# 4_periferals.net
KiCad netlist of a schematic drawn in Altium Designer
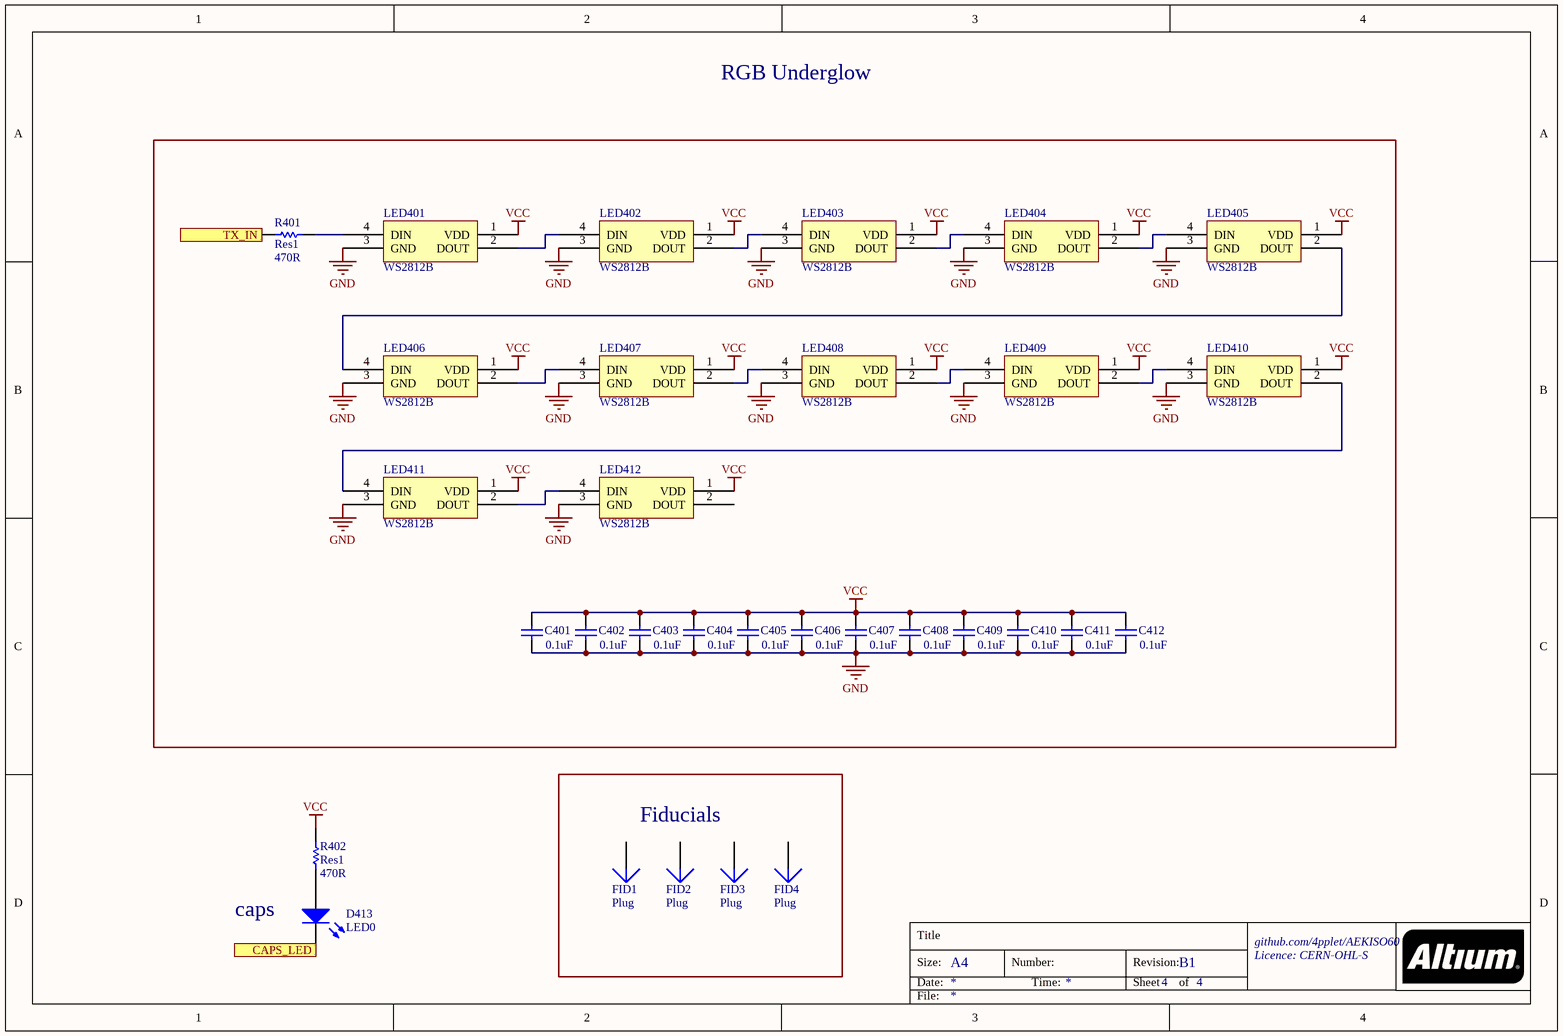
[diagram p0: 4_periferals.SchDoc]

(export (version "E")
  (design (tool "Eeschema 10.0.6"))
  (components
    (comp (ref "C401")
      (value "0.1uF")
      (footprint "C0603[1608]")
      (description "Capacitor")
      (fields (field (name "LCSC PART #") "C14663") (field (name "MRF.PART") "CC0603KRX7R9BB104"))
      (libsource (lib "Miscellaneous Devices") (part "Cap"))
    )
    (comp (ref "C402")
      (value "0.1uF")
      (footprint "C0603[1608]")
      (description "Capacitor")
      (fields (field (name "LCSC PART #") "C14663") (field (name "MRF.PART") "CC0603KRX7R9BB104"))
      (libsource (lib "Miscellaneous Devices") (part "Cap"))
    )
    (comp (ref "C403")
      (value "0.1uF")
      (footprint "C0603[1608]")
      (description "Capacitor")
      (fields (field (name "LCSC PART #") "C14663") (field (name "MRF.PART") "CC0603KRX7R9BB104"))
      (libsource (lib "Miscellaneous Devices") (part "Cap"))
    )
    (comp (ref "C404")
      (value "0.1uF")
      (footprint "C0603[1608]")
      (description "Capacitor")
      (fields (field (name "LCSC PART #") "C14663") (field (name "MRF.PART") "CC0603KRX7R9BB104"))
      (libsource (lib "Miscellaneous Devices") (part "Cap"))
    )
    (comp (ref "C405")
      (value "0.1uF")
      (footprint "C0603[1608]")
      (description "Capacitor")
      (fields (field (name "LCSC PART #") "C14663") (field (name "MRF.PART") "CC0603KRX7R9BB104"))
      (libsource (lib "Miscellaneous Devices") (part "Cap"))
    )
    (comp (ref "C406")
      (value "0.1uF")
      (footprint "C0603[1608]")
      (description "Capacitor")
      (fields (field (name "LCSC PART #") "C14663") (field (name "MRF.PART") "CC0603KRX7R9BB104"))
      (libsource (lib "Miscellaneous Devices") (part "Cap"))
    )
    (comp (ref "C407")
      (value "0.1uF")
      (footprint "C0603[1608]")
      (description "Capacitor")
      (fields (field (name "LCSC PART #") "C14663") (field (name "MRF.PART") "CC0603KRX7R9BB104"))
      (libsource (lib "Miscellaneous Devices") (part "Cap"))
    )
    (comp (ref "C408")
      (value "0.1uF")
      (footprint "C0603[1608]")
      (description "Capacitor")
      (fields (field (name "LCSC PART #") "C14663") (field (name "MRF.PART") "CC0603KRX7R9BB104"))
      (libsource (lib "Miscellaneous Devices") (part "Cap"))
    )
    (comp (ref "C409")
      (value "0.1uF")
      (footprint "C0603[1608]")
      (description "Capacitor")
      (fields (field (name "LCSC PART #") "C14663") (field (name "MRF.PART") "CC0603KRX7R9BB104"))
      (libsource (lib "Miscellaneous Devices") (part "Cap"))
    )
    (comp (ref "C410")
      (value "0.1uF")
      (footprint "C0603[1608]")
      (description "Capacitor")
      (fields (field (name "LCSC PART #") "C14663") (field (name "MRF.PART") "CC0603KRX7R9BB104"))
      (libsource (lib "Miscellaneous Devices") (part "Cap"))
    )
    (comp (ref "C411")
      (value "0.1uF")
      (footprint "C0603[1608]")
      (description "Capacitor")
      (fields (field (name "LCSC PART #") "C14663") (field (name "MRF.PART") "CC0603KRX7R9BB104"))
      (libsource (lib "Miscellaneous Devices") (part "Cap"))
    )
    (comp (ref "C412")
      (value "0.1uF")
      (footprint "C0603[1608]")
      (description "Capacitor")
      (fields (field (name "LCSC PART #") "C14663") (field (name "MRF.PART") "CC0603KRX7R9BB104"))
      (libsource (lib "Miscellaneous Devices") (part "Cap"))
    )
    (comp (ref "D413")
      (value "LED0")
      (footprint "SWITCH_LED - 1U")
      (description "Typical INFRARED GaAs LED")
      (libsource (lib "Miscellaneous Devices") (part "LED0"))
    )
    (comp (ref "FID1")
      (value "Plug")
      (footprint "Fiducial_Nordic")
      (libsource (lib "Miscellaneous Connectors") (part "Plug"))
    )
    (comp (ref "FID2")
      (value "Plug")
      (footprint "Fiducial_Nordic")
      (libsource (lib "Miscellaneous Connectors") (part "Plug"))
    )
    (comp (ref "FID3")
      (value "Plug")
      (footprint "Fiducial_Nordic")
      (libsource (lib "Miscellaneous Connectors") (part "Plug"))
    )
    (comp (ref "FID4")
      (value "Plug")
      (footprint "Fiducial_Nordic")
      (libsource (lib "Miscellaneous Connectors") (part "Plug"))
    )
    (comp (ref "LED401")
      (value "WS2812B")
      (footprint "WS2812B")
      (fields (field (name "LCSC PART #") "C2920042") (field (name "MRF.PART") "WS2812E-V5"))
      (libsource (lib "Keebs") (part "WS2812B"))
    )
    (comp (ref "LED402")
      (value "WS2812B")
      (footprint "WS2812B")
      (fields (field (name "LCSC PART #") "C2920042") (field (name "MRF.PART") "WS2812E-V5"))
      (libsource (lib "Keebs") (part "WS2812B"))
    )
    (comp (ref "LED403")
      (value "WS2812B")
      (footprint "WS2812B")
      (fields (field (name "LCSC PART #") "C2920042") (field (name "MRF.PART") "WS2812E-V5"))
      (libsource (lib "Keebs") (part "WS2812B"))
    )
    (comp (ref "LED404")
      (value "WS2812B")
      (footprint "WS2812B")
      (fields (field (name "LCSC PART #") "C2920042") (field (name "MRF.PART") "WS2812E-V5"))
      (libsource (lib "Keebs") (part "WS2812B"))
    )
    (comp (ref "LED405")
      (value "WS2812B")
      (footprint "WS2812B")
      (fields (field (name "LCSC PART #") "C2920042") (field (name "MRF.PART") "WS2812E-V5"))
      (libsource (lib "Keebs") (part "WS2812B"))
    )
    (comp (ref "LED406")
      (value "WS2812B")
      (footprint "WS2812B")
      (fields (field (name "LCSC PART #") "C2920042") (field (name "MRF.PART") "WS2812E-V5"))
      (libsource (lib "Keebs") (part "WS2812B"))
    )
    (comp (ref "LED407")
      (value "WS2812B")
      (footprint "WS2812B")
      (fields (field (name "LCSC PART #") "C2920042") (field (name "MRF.PART") "WS2812E-V5"))
      (libsource (lib "Keebs") (part "WS2812B"))
    )
    (comp (ref "LED408")
      (value "WS2812B")
      (footprint "WS2812B")
      (fields (field (name "LCSC PART #") "C2920042") (field (name "MRF.PART") "WS2812E-V5"))
      (libsource (lib "Keebs") (part "WS2812B"))
    )
    (comp (ref "LED409")
      (value "WS2812B")
      (footprint "WS2812B")
      (fields (field (name "LCSC PART #") "C2920042") (field (name "MRF.PART") "WS2812E-V5"))
      (libsource (lib "Keebs") (part "WS2812B"))
    )
    (comp (ref "LED410")
      (value "WS2812B")
      (footprint "WS2812B")
      (fields (field (name "LCSC PART #") "C2920042") (field (name "MRF.PART") "WS2812E-V5"))
      (libsource (lib "Keebs") (part "WS2812B"))
    )
    (comp (ref "LED411")
      (value "WS2812B")
      (footprint "WS2812B")
      (fields (field (name "LCSC PART #") "C2920042") (field (name "MRF.PART") "WS2812E-V5"))
      (libsource (lib "Keebs") (part "WS2812B"))
    )
    (comp (ref "LED412")
      (value "WS2812B")
      (footprint "WS2812B")
      (fields (field (name "LCSC PART #") "C2920042") (field (name "MRF.PART") "WS2812E-V5"))
      (libsource (lib "Keebs") (part "WS2812B"))
    )
    (comp (ref "R401")
      (value "Res1")
      (footprint "R0603[1608]")
      (description "Resistor")
      (fields
        (field (name "ALTIUM_VALUE") "470R")
        (field (name "LCSC PART #") "C23179")
        (field (name "MRF.PART") "0603WAF4700T5E")
      )
      (libsource (lib "Miscellaneous Devices") (part "Res1"))
    )
    (comp (ref "R402")
      (value "Res1")
      (footprint "R0603[1608] - THT")
      (description "Resistor")
      (fields
        (field (name "ALTIUM_VALUE") "470R")
        (field (name "LCSC PART #") "C23179")
        (field (name "MRF.PART") "0603WAF4700T5E")
      )
      (libsource (lib "Miscellaneous Devices") (part "Res1"))
    )
  )
  (nets
    (net (code "1") (name "/CAPS_LED") (class "Default")
      (node (ref "D413") (pin "2") (pinfunction "K_2") (pintype "passive"))
    )
    (net (code "2") (name "/TX_IN") (class "Default")
      (node (ref "R401") (pin "1") (pinfunction "1_1") (pintype "passive"))
    )
    (net (code "3") (name "GND") (class "Default")
      (node (ref "C401") (pin "1") (pinfunction "1_1") (pintype "passive"))
      (node (ref "C402") (pin "1") (pinfunction "1_1") (pintype "passive"))
      (node (ref "C403") (pin "1") (pinfunction "1_1") (pintype "passive"))
      (node (ref "C404") (pin "1") (pinfunction "1_1") (pintype "passive"))
      (node (ref "C405") (pin "1") (pinfunction "1_1") (pintype "passive"))
      (node (ref "C406") (pin "1") (pinfunction "1_1") (pintype "passive"))
      (node (ref "C407") (pin "1") (pinfunction "1_1") (pintype "passive"))
      (node (ref "C408") (pin "1") (pinfunction "1_1") (pintype "passive"))
      (node (ref "C409") (pin "1") (pinfunction "1_1") (pintype "passive"))
      (node (ref "C410") (pin "1") (pinfunction "1_1") (pintype "passive"))
      (node (ref "C411") (pin "1") (pinfunction "1_1") (pintype "passive"))
      (node (ref "C412") (pin "1") (pinfunction "1_1") (pintype "passive"))
      (node (ref "LED401") (pin "3") (pinfunction "GND_3") (pintype "passive"))
      (node (ref "LED402") (pin "3") (pinfunction "GND_3") (pintype "passive"))
      (node (ref "LED403") (pin "3") (pinfunction "GND_3") (pintype "passive"))
      (node (ref "LED404") (pin "3") (pinfunction "GND_3") (pintype "passive"))
      (node (ref "LED405") (pin "3") (pinfunction "GND_3") (pintype "passive"))
      (node (ref "LED406") (pin "3") (pinfunction "GND_3") (pintype "passive"))
      (node (ref "LED407") (pin "3") (pinfunction "GND_3") (pintype "passive"))
      (node (ref "LED408") (pin "3") (pinfunction "GND_3") (pintype "passive"))
      (node (ref "LED409") (pin "3") (pinfunction "GND_3") (pintype "passive"))
      (node (ref "LED410") (pin "3") (pinfunction "GND_3") (pintype "passive"))
      (node (ref "LED411") (pin "3") (pinfunction "GND_3") (pintype "passive"))
      (node (ref "LED412") (pin "3") (pinfunction "GND_3") (pintype "passive"))
    )
    (net (code "4") (name "Net-(D413-A)") (class "Default")
      (node (ref "D413") (pin "1") (pinfunction "A_1") (pintype "passive"))
      (node (ref "R402") (pin "1") (pinfunction "1_1") (pintype "passive"))
    )
    (net (code "5") (name "Net-(LED401-DIN)") (class "Default")
      (node (ref "LED401") (pin "4") (pinfunction "DIN_4") (pintype "passive"))
      (node (ref "R401") (pin "2") (pinfunction "2_2") (pintype "passive"))
    )
    (net (code "6") (name "Net-(LED401-DOUT)") (class "Default")
      (node (ref "LED401") (pin "2") (pinfunction "DOUT_2") (pintype "passive"))
      (node (ref "LED402") (pin "4") (pinfunction "DIN_4") (pintype "passive"))
    )
    (net (code "7") (name "Net-(LED402-DOUT)") (class "Default")
      (node (ref "LED402") (pin "2") (pinfunction "DOUT_2") (pintype "passive"))
      (node (ref "LED403") (pin "4") (pinfunction "DIN_4") (pintype "passive"))
    )
    (net (code "8") (name "Net-(LED403-DOUT)") (class "Default")
      (node (ref "LED403") (pin "2") (pinfunction "DOUT_2") (pintype "passive"))
      (node (ref "LED404") (pin "4") (pinfunction "DIN_4") (pintype "passive"))
    )
    (net (code "9") (name "Net-(LED404-DOUT)") (class "Default")
      (node (ref "LED404") (pin "2") (pinfunction "DOUT_2") (pintype "passive"))
      (node (ref "LED405") (pin "4") (pinfunction "DIN_4") (pintype "passive"))
    )
    (net (code "10") (name "Net-(LED405-DOUT)") (class "Default")
      (node (ref "LED405") (pin "2") (pinfunction "DOUT_2") (pintype "passive"))
      (node (ref "LED406") (pin "4") (pinfunction "DIN_4") (pintype "passive"))
    )
    (net (code "11") (name "Net-(LED406-DOUT)") (class "Default")
      (node (ref "LED406") (pin "2") (pinfunction "DOUT_2") (pintype "passive"))
      (node (ref "LED407") (pin "4") (pinfunction "DIN_4") (pintype "passive"))
    )
    (net (code "12") (name "Net-(LED407-DOUT)") (class "Default")
      (node (ref "LED407") (pin "2") (pinfunction "DOUT_2") (pintype "passive"))
      (node (ref "LED408") (pin "4") (pinfunction "DIN_4") (pintype "passive"))
    )
    (net (code "13") (name "Net-(LED408-DOUT)") (class "Default")
      (node (ref "LED408") (pin "2") (pinfunction "DOUT_2") (pintype "passive"))
      (node (ref "LED409") (pin "4") (pinfunction "DIN_4") (pintype "passive"))
    )
    (net (code "14") (name "Net-(LED409-DOUT)") (class "Default")
      (node (ref "LED409") (pin "2") (pinfunction "DOUT_2") (pintype "passive"))
      (node (ref "LED410") (pin "4") (pinfunction "DIN_4") (pintype "passive"))
    )
    (net (code "15") (name "Net-(LED410-DOUT)") (class "Default")
      (node (ref "LED410") (pin "2") (pinfunction "DOUT_2") (pintype "passive"))
      (node (ref "LED411") (pin "4") (pinfunction "DIN_4") (pintype "passive"))
    )
    (net (code "16") (name "Net-(LED411-DOUT)") (class "Default")
      (node (ref "LED411") (pin "2") (pinfunction "DOUT_2") (pintype "passive"))
      (node (ref "LED412") (pin "4") (pinfunction "DIN_4") (pintype "passive"))
    )
    (net (code "17") (name "VCC") (class "Default")
      (node (ref "C401") (pin "2") (pinfunction "2_2") (pintype "passive"))
      (node (ref "C402") (pin "2") (pinfunction "2_2") (pintype "passive"))
      (node (ref "C403") (pin "2") (pinfunction "2_2") (pintype "passive"))
      (node (ref "C404") (pin "2") (pinfunction "2_2") (pintype "passive"))
      (node (ref "C405") (pin "2") (pinfunction "2_2") (pintype "passive"))
      (node (ref "C406") (pin "2") (pinfunction "2_2") (pintype "passive"))
      (node (ref "C407") (pin "2") (pinfunction "2_2") (pintype "passive"))
      (node (ref "C408") (pin "2") (pinfunction "2_2") (pintype "passive"))
      (node (ref "C409") (pin "2") (pinfunction "2_2") (pintype "passive"))
      (node (ref "C410") (pin "2") (pinfunction "2_2") (pintype "passive"))
      (node (ref "C411") (pin "2") (pinfunction "2_2") (pintype "passive"))
      (node (ref "C412") (pin "2") (pinfunction "2_2") (pintype "passive"))
      (node (ref "LED401") (pin "1") (pinfunction "VDD_1") (pintype "passive"))
      (node (ref "LED402") (pin "1") (pinfunction "VDD_1") (pintype "passive"))
      (node (ref "LED403") (pin "1") (pinfunction "VDD_1") (pintype "passive"))
      (node (ref "LED404") (pin "1") (pinfunction "VDD_1") (pintype "passive"))
      (node (ref "LED405") (pin "1") (pinfunction "VDD_1") (pintype "passive"))
      (node (ref "LED406") (pin "1") (pinfunction "VDD_1") (pintype "passive"))
      (node (ref "LED407") (pin "1") (pinfunction "VDD_1") (pintype "passive"))
      (node (ref "LED408") (pin "1") (pinfunction "VDD_1") (pintype "passive"))
      (node (ref "LED409") (pin "1") (pinfunction "VDD_1") (pintype "passive"))
      (node (ref "LED410") (pin "1") (pinfunction "VDD_1") (pintype "passive"))
      (node (ref "LED411") (pin "1") (pinfunction "VDD_1") (pintype "passive"))
      (node (ref "LED412") (pin "1") (pinfunction "VDD_1") (pintype "passive"))
      (node (ref "R402") (pin "2") (pinfunction "2_2") (pintype "passive"))
    )
    (net (code "18") (name "unconnected-(FID1-Pad1)") (class "Default")
      (node (ref "FID1") (pin "1") (pinfunction "1_1") (pintype "passive"))
    )
    (net (code "19") (name "unconnected-(FID2-Pad1)") (class "Default")
      (node (ref "FID2") (pin "1") (pinfunction "1_1") (pintype "passive"))
    )
    (net (code "20") (name "unconnected-(FID3-Pad1)") (class "Default")
      (node (ref "FID3") (pin "1") (pinfunction "1_1") (pintype "passive"))
    )
    (net (code "21") (name "unconnected-(FID4-Pad1)") (class "Default")
      (node (ref "FID4") (pin "1") (pinfunction "1_1") (pintype "passive"))
    )
    (net (code "22") (name "unconnected-(LED412-DOUT-Pad2)") (class "Default")
      (node (ref "LED412") (pin "2") (pinfunction "DOUT_2") (pintype "passive"))
    )
  )
)
